# Soundtrap_IMU_board_v4_RXTX_switch.net
KiCad netlist of a schematic drawn in EAGLE
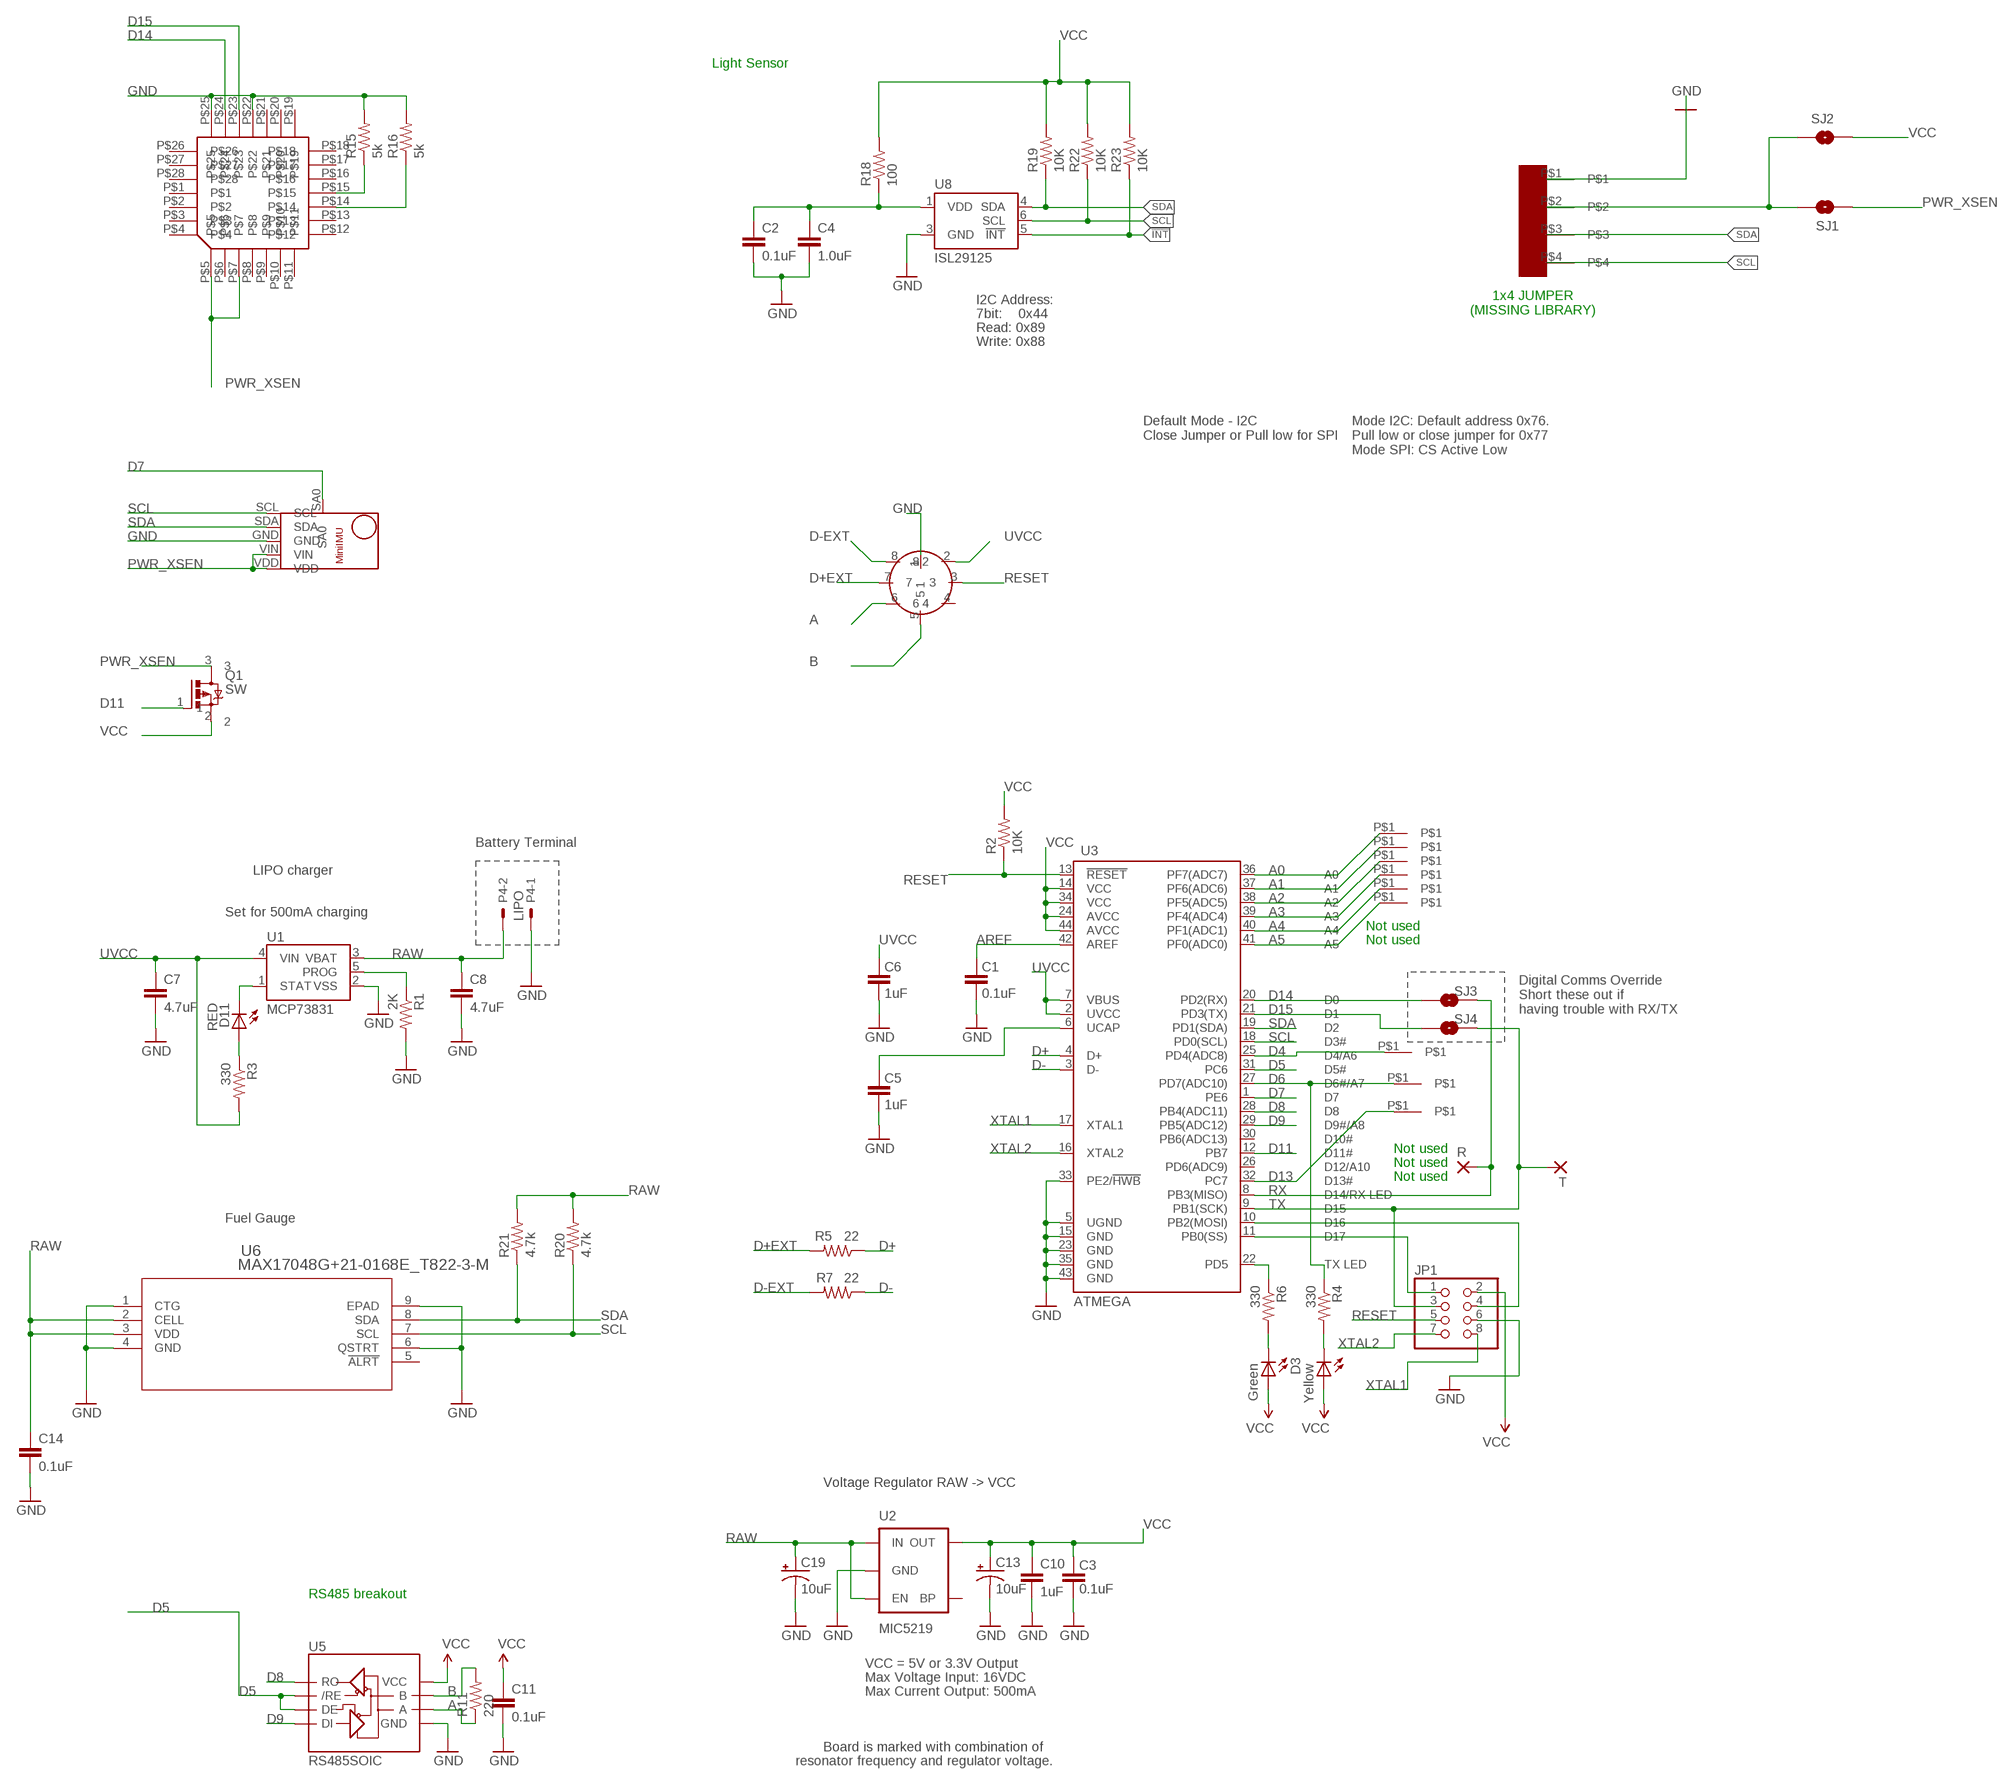
[diagram p0: schematic, sheet 1]

(export (version "E")
  (design (tool "Eeschema 10.0.6"))
  (components
    (comp (ref "C1")
      (value "0.1uF")
      (footprint "eagle-import:0603-CAP")
      (libsource (lib "eagle-import") (part "CAP0603-CAP"))
    )
    (comp (ref "C2")
      (value "0.1uF")
      (footprint "eagle-import:0603-CAP")
      (libsource (lib "eagle-import") (part "0.1UF-25V(+80/-20%)(0603)"))
    )
    (comp (ref "C3")
      (value "0.1uF")
      (footprint "eagle-import:0603-CAP")
      (libsource (lib "eagle-import") (part "CAP0603-CAP"))
    )
    (comp (ref "C4")
      (value "1.0uF")
      (footprint "eagle-import:0603-CAP")
      (libsource (lib "eagle-import") (part "1.0UF-16V-10%(0603)"))
    )
    (comp (ref "C5")
      (value "1uF")
      (footprint "eagle-import:0603-CAP")
      (libsource (lib "eagle-import") (part "CAP0603-CAP"))
    )
    (comp (ref "C6")
      (value "1uF")
      (footprint "eagle-import:0603-CAP")
      (libsource (lib "eagle-import") (part "CAP0603-CAP"))
    )
    (comp (ref "C7")
      (value "4.7uF")
      (footprint "eagle-import:0402-CAP")
      (libsource (lib "eagle-import") (part "CAP0402-CAP"))
    )
    (comp (ref "C8")
      (value "4.7uF")
      (footprint "eagle-import:0402-CAP")
      (libsource (lib "eagle-import") (part "CAP0402-CAP"))
    )
    (comp (ref "C10")
      (value "1uF")
      (footprint "eagle-import:0603-CAP")
      (libsource (lib "eagle-import") (part "CAP0603-CAP"))
    )
    (comp (ref "C11")
      (value "0.1uF")
      (footprint "eagle-import:0402-CAP")
      (libsource (lib "eagle-import") (part "CAP0402-CAP"))
    )
    (comp (ref "C13")
      (value "10uF")
      (footprint "eagle-import:EIA3216")
      (libsource (lib "eagle-import") (part "CAP_POL1206"))
    )
    (comp (ref "C14")
      (value "0.1uF")
      (footprint "eagle-import:0402-CAP")
      (libsource (lib "eagle-import") (part "CAP0402-CAP"))
    )
    (comp (ref "C19")
      (value "10uF")
      (footprint "eagle-import:EIA3216")
      (libsource (lib "eagle-import") (part "CAP_POL1206"))
    )
    (comp (ref "D1")
      (value "Yellow")
      (footprint "eagle-import:LED-0603")
      (libsource (lib "eagle-import") (part "LED0603"))
    )
    (comp (ref "D3")
      (value "Green")
      (footprint "eagle-import:LED-0603")
      (libsource (lib "eagle-import") (part "LED0603"))
    )
    (comp (ref "D11")
      (value "RED")
      (footprint "eagle-import:LED-0603")
      (libsource (lib "eagle-import") (part "LED0603"))
    )
    (comp (ref "JP1")
      (value "PINHD-2X4")
      (footprint "eagle-import:2X04")
      (libsource (lib "eagle-import") (part "PINHD-2X4"))
    )
    (comp (ref "P1")
      (value "SUBCON_MICRO_8_EDGE_ORDERED")
      (footprint "eagle-import:SUBCON_MICRO_8_EDGE")
      (libsource (lib "eagle-import") (part "SUBCON_MICRO_8_EDGE_ORDERED"))
    )
    (comp (ref "P2")
      (value "MINI_IMU")
      (footprint "eagle-import:MINI_IMU")
      (libsource (lib "eagle-import") (part "MINI_IMU"))
    )
    (comp (ref "P3")
      (value "EXT_PRES")
      (footprint "eagle-import:EXT_PRES")
      (libsource (lib "eagle-import") (part "EXT_PRES"))
    )
    (comp (ref "P4")
      (value "LIPO")
      (footprint "eagle-import:22-23-2021")
      (fields (field (name "MF") "MOLEX") (field (name "MPN") "22-23-2021"))
      (libsource (lib "eagle-import") (part "22-23-2021"))
    )
    (comp (ref "Q1")
      (value "SW")
      (footprint "eagle-import:SOT23")
      (libsource (lib "eagle-import") (part "INFINEON_BSS84P"))
    )
    (comp (ref "R")
      (value "1,6/0,9")
      (footprint "eagle-import:1,6_0,9")
      (libsource (lib "eagle-import") (part "1,6/0,9"))
    )
    (comp (ref "R1")
      (value "2K")
      (footprint "eagle-import:0402-RES")
      (libsource (lib "eagle-import") (part "RESISTOR0402-RES"))
    )
    (comp (ref "R2")
      (value "10K")
      (footprint "eagle-import:0603-RES")
      (libsource (lib "eagle-import") (part "RESISTOR0603-RES"))
    )
    (comp (ref "R3")
      (value "330")
      (footprint "eagle-import:0402-RES")
      (libsource (lib "eagle-import") (part "RESISTOR0402-RES"))
    )
    (comp (ref "R4")
      (value "330")
      (footprint "eagle-import:0603-RES")
      (libsource (lib "eagle-import") (part "RESISTOR0603-RES"))
    )
    (comp (ref "R5")
      (value "22")
      (footprint "eagle-import:0603-RES")
      (libsource (lib "eagle-import") (part "RESISTOR0603-RES"))
    )
    (comp (ref "R6")
      (value "330")
      (footprint "eagle-import:0603-RES")
      (libsource (lib "eagle-import") (part "RESISTOR0603-RES"))
    )
    (comp (ref "R7")
      (value "22")
      (footprint "eagle-import:0603-RES")
      (libsource (lib "eagle-import") (part "RESISTOR0603-RES"))
    )
    (comp (ref "R11")
      (value "220")
      (footprint "eagle-import:0402-RES")
      (libsource (lib "eagle-import") (part "RESISTOR0402-RES"))
    )
    (comp (ref "R15")
      (value "5k")
      (footprint "eagle-import:R0603")
      (libsource (lib "eagle-import") (part "R-US_R0603"))
    )
    (comp (ref "R16")
      (value "5k")
      (footprint "eagle-import:R0603")
      (libsource (lib "eagle-import") (part "R-US_R0603"))
    )
    (comp (ref "R18")
      (value "100")
      (footprint "eagle-import:0603-RES")
      (libsource (lib "eagle-import") (part "100OHM1/10W1%(0603)"))
    )
    (comp (ref "R19")
      (value "10K")
      (footprint "eagle-import:0603-RES")
      (libsource (lib "eagle-import") (part "10KOHM1/10W1%(0603)0603"))
    )
    (comp (ref "R20")
      (value "4.7k")
      (footprint "eagle-import:0402-RES")
      (libsource (lib "eagle-import") (part "RESISTOR0402-RES"))
    )
    (comp (ref "R21")
      (value "4.7k")
      (footprint "eagle-import:0402-RES")
      (libsource (lib "eagle-import") (part "RESISTOR0402-RES"))
    )
    (comp (ref "R22")
      (value "10K")
      (footprint "eagle-import:0603-RES")
      (libsource (lib "eagle-import") (part "10KOHM1/10W1%(0603)0603"))
    )
    (comp (ref "R23")
      (value "10K")
      (footprint "eagle-import:0603-RES")
      (libsource (lib "eagle-import") (part "10KOHM1/10W1%(0603)0603"))
    )
    (comp (ref "SJ1")
      (value "SJ1")
      (footprint "eagle-import:SJ_2S-NO")
      (libsource (lib "eagle-import") (part "SOLDERJUMPERNO"))
    )
    (comp (ref "SJ2")
      (value "3v3")
      (footprint "eagle-import:SJ_2S-NO")
      (libsource (lib "eagle-import") (part "SOLDERJUMPERNO"))
    )
    (comp (ref "SJ3")
      (value "SJ1")
      (footprint "eagle-import:SJ_2S-NO")
      (libsource (lib "eagle-import") (part "SOLDERJUMPERNO"))
    )
    (comp (ref "SJ4")
      (value "SJ1")
      (footprint "eagle-import:SJ_2S-NO")
      (libsource (lib "eagle-import") (part "SOLDERJUMPERNO"))
    )
    (comp (ref "T")
      (value "1,6/0,9")
      (footprint "eagle-import:1,6_0,9")
      (libsource (lib "eagle-import") (part "1,6/0,9"))
    )
    (comp (ref "U$5")
      (value "D4")
      (footprint "eagle-import:TEST_POINT")
      (libsource (lib "eagle-import") (part "TEST_POINT"))
    )
    (comp (ref "U$6")
      (value "TEST_POINT")
      (footprint "eagle-import:TEST_POINT")
      (libsource (lib "eagle-import") (part "TEST_POINT"))
    )
    (comp (ref "U$7")
      (value "TEST_POINT")
      (footprint "eagle-import:TEST_POINT")
      (libsource (lib "eagle-import") (part "TEST_POINT"))
    )
    (comp (ref "U$8")
      (value "TEST_POINT")
      (footprint "eagle-import:TEST_POINT")
      (libsource (lib "eagle-import") (part "TEST_POINT"))
    )
    (comp (ref "U$9")
      (value "TEST_POINT")
      (footprint "eagle-import:TEST_POINT")
      (libsource (lib "eagle-import") (part "TEST_POINT"))
    )
    (comp (ref "U$10")
      (value "TEST_POINT")
      (footprint "eagle-import:TEST_POINT")
      (libsource (lib "eagle-import") (part "TEST_POINT"))
    )
    (comp (ref "U$11")
      (value "TEST_POINT")
      (footprint "eagle-import:TEST_POINT")
      (libsource (lib "eagle-import") (part "TEST_POINT"))
    )
    (comp (ref "U$12")
      (value "TEST_POINT")
      (footprint "eagle-import:TEST_POINT")
      (libsource (lib "eagle-import") (part "TEST_POINT"))
    )
    (comp (ref "U$13")
      (value "TEST_POINT")
      (footprint "eagle-import:TEST_POINT")
      (libsource (lib "eagle-import") (part "TEST_POINT"))
    )
    (comp (ref "U1")
      (value "MCP73831")
      (footprint "eagle-import:SOT23-5")
      (libsource (lib "eagle-import") (part "MCP73831"))
    )
    (comp (ref "U2")
      (value "MIC5219")
      (footprint "eagle-import:SOT23-5")
      (libsource (lib "eagle-import") (part "V_REG_LDOSMD"))
    )
    (comp (ref "U3")
      (value "ATMEGA")
      (footprint "eagle-import:QFN-44-NOPAD_1_1-OUTFAKES")
      (libsource (lib "eagle-import") (part "ATMEGA32U4OUTFAKES"))
    )
    (comp (ref "U5")
      (value "RS485SOIC")
      (footprint "eagle-import:SO08")
      (libsource (lib "eagle-import") (part "RS485SOIC"))
    )
    (comp (ref "U6")
      (value "MAX17048G+21-0168E_T822-3-M")
      (footprint "eagle-import:21-0168E_T822-3-M")
      (fields (field (name "MANUFACTURER_PART_NUMBER") "MAX17048G+"))
      (libsource (lib "eagle-import") (part "MAX17048G+21-0168E_T822-3-M"))
    )
    (comp (ref "U7")
      (value "XSENSE")
      (footprint "eagle-import:MC-28PLCC-SMT")
      (libsource (lib "eagle-import") (part "XSENSE"))
    )
    (comp (ref "U8")
      (value "ISL29125")
      (footprint "eagle-import:ODFN-LD-6")
      (libsource (lib "eagle-import") (part "ISL29125"))
    )
  )
  (nets
    (net (code "1") (name "/A") (class "Default")
      (node (ref "P1") (pin "6") (pinfunction "6_6") (pintype "bidirectional"))
      (node (ref "R11") (pin "1") (pinfunction "1_1") (pintype "passive"))
      (node (ref "U5") (pin "6") (pinfunction "A_6") (pintype "bidirectional"))
    )
    (net (code "2") (name "/A0") (class "Default")
      (node (ref "U$8") (pin "P$1") (pinfunction "P$1_P$1") (pintype "bidirectional"))
      (node (ref "U3") (pin "36") (pinfunction "PF7(ADC7)_36") (pintype "bidirectional"))
    )
    (net (code "3") (name "/A1") (class "Default")
      (node (ref "U$9") (pin "P$1") (pinfunction "P$1_P$1") (pintype "bidirectional"))
      (node (ref "U3") (pin "37") (pinfunction "PF6(ADC6)_37") (pintype "bidirectional"))
    )
    (net (code "4") (name "/A2") (class "Default")
      (node (ref "U$10") (pin "P$1") (pinfunction "P$1_P$1") (pintype "bidirectional"))
      (node (ref "U3") (pin "38") (pinfunction "PF5(ADC5)_38") (pintype "bidirectional"))
    )
    (net (code "5") (name "/A3") (class "Default")
      (node (ref "U$11") (pin "P$1") (pinfunction "P$1_P$1") (pintype "bidirectional"))
      (node (ref "U3") (pin "39") (pinfunction "PF4(ADC4)_39") (pintype "bidirectional"))
    )
    (net (code "6") (name "/A4") (class "Default")
      (node (ref "U$12") (pin "P$1") (pinfunction "P$1_P$1") (pintype "bidirectional"))
      (node (ref "U3") (pin "40") (pinfunction "PF1(ADC1)_40") (pintype "bidirectional"))
    )
    (net (code "7") (name "/A5") (class "Default")
      (node (ref "U$13") (pin "P$1") (pinfunction "P$1_P$1") (pintype "bidirectional"))
      (node (ref "U3") (pin "41") (pinfunction "PF0(ADC0)_41") (pintype "bidirectional"))
    )
    (net (code "8") (name "/AREF") (class "Default")
      (node (ref "C1") (pin "2") (pinfunction "2_2") (pintype "passive"))
      (node (ref "U3") (pin "42") (pinfunction "AREF_42") (pintype "bidirectional"))
    )
    (net (code "9") (name "/B") (class "Default")
      (node (ref "P1") (pin "5") (pinfunction "5_5") (pintype "bidirectional"))
      (node (ref "R11") (pin "2") (pinfunction "2_2") (pintype "passive"))
      (node (ref "U5") (pin "7") (pinfunction "B_7") (pintype "bidirectional"))
    )
    (net (code "10") (name "/D+") (class "Default")
      (node (ref "R5") (pin "1") (pinfunction "1_1") (pintype "passive"))
      (node (ref "U3") (pin "4") (pinfunction "D+_4") (pintype "bidirectional"))
    )
    (net (code "11") (name "/D+EXT") (class "Default")
      (node (ref "P1") (pin "7") (pinfunction "7_7") (pintype "bidirectional"))
      (node (ref "R5") (pin "2") (pinfunction "2_2") (pintype "passive"))
    )
    (net (code "12") (name "/D-") (class "Default")
      (node (ref "R7") (pin "1") (pinfunction "1_1") (pintype "passive"))
      (node (ref "U3") (pin "3") (pinfunction "D-_3") (pintype "bidirectional"))
    )
    (net (code "13") (name "/D-EXT") (class "Default")
      (node (ref "P1") (pin "8") (pinfunction "8_8") (pintype "bidirectional"))
      (node (ref "R7") (pin "2") (pinfunction "2_2") (pintype "passive"))
    )
    (net (code "14") (name "/D4") (class "Default")
      (node (ref "U$5") (pin "P$1") (pinfunction "P$1_P$1") (pintype "bidirectional"))
      (node (ref "U3") (pin "25") (pinfunction "PD4(ADC8)_25") (pintype "bidirectional"))
    )
    (net (code "15") (name "/D5") (class "Default")
      (node (ref "U3") (pin "31") (pinfunction "PC6_31") (pintype "bidirectional"))
      (node (ref "U5") (pin "2") (pinfunction "/RE_2") (pintype "bidirectional"))
      (node (ref "U5") (pin "3") (pinfunction "DE_3") (pintype "bidirectional"))
    )
    (net (code "16") (name "/D6") (class "Default")
      (node (ref "R4") (pin "1") (pinfunction "1_1") (pintype "passive"))
      (node (ref "U$6") (pin "P$1") (pinfunction "P$1_P$1") (pintype "bidirectional"))
      (node (ref "U3") (pin "27") (pinfunction "PD7(ADC10)_27") (pintype "bidirectional"))
    )
    (net (code "17") (name "/D7") (class "Default")
      (node (ref "P2") (pin "SA0") (pinfunction "SA0_SA0") (pintype "bidirectional"))
      (node (ref "U3") (pin "1") (pinfunction "PE6_1") (pintype "bidirectional"))
    )
    (net (code "18") (name "/D8") (class "Default")
      (node (ref "U3") (pin "28") (pinfunction "PB4(ADC11)_28") (pintype "bidirectional"))
      (node (ref "U5") (pin "1") (pinfunction "RO_1") (pintype "bidirectional"))
    )
    (net (code "19") (name "/D9") (class "Default")
      (node (ref "U3") (pin "29") (pinfunction "PB5(ADC12)_29") (pintype "bidirectional"))
      (node (ref "U5") (pin "4") (pinfunction "DI_4") (pintype "bidirectional"))
    )
    (net (code "20") (name "/D11") (class "Default")
      (node (ref "Q1") (pin "1") (pinfunction "1_1") (pintype "input"))
      (node (ref "U3") (pin "12") (pinfunction "PB7_12") (pintype "bidirectional"))
    )
    (net (code "21") (name "/D13") (class "Default")
      (node (ref "U$7") (pin "P$1") (pinfunction "P$1_P$1") (pintype "bidirectional"))
      (node (ref "U3") (pin "32") (pinfunction "PC7_32") (pintype "bidirectional"))
    )
    (net (code "22") (name "/D14") (class "Default")
      (node (ref "SJ3") (pin "2") (pinfunction "2_2") (pintype "passive"))
      (node (ref "U3") (pin "20") (pinfunction "PD2(RX)_20") (pintype "bidirectional"))
      (node (ref "U7") (pin "P$24") (pinfunction "P$24_P$24") (pintype "bidirectional"))
    )
    (net (code "23") (name "/D15") (class "Default")
      (node (ref "SJ4") (pin "2") (pinfunction "2_2") (pintype "passive"))
      (node (ref "U3") (pin "21") (pinfunction "PD3(TX)_21") (pintype "bidirectional"))
      (node (ref "U7") (pin "P$23") (pinfunction "P$23_P$23") (pintype "bidirectional"))
    )
    (net (code "24") (name "/PWR_XSEN") (class "Default")
      (node (ref "P2") (pin "VDD") (pinfunction "VDD_VDD") (pintype "power_in"))
      (node (ref "P2") (pin "VIN") (pinfunction "VIN_VIN") (pintype "power_in"))
      (node (ref "Q1") (pin "3") (pinfunction "3_3") (pintype "output"))
      (node (ref "SJ1") (pin "1") (pinfunction "1_1") (pintype "passive"))
      (node (ref "U7") (pin "P$5") (pinfunction "P$5_P$5") (pintype "bidirectional"))
      (node (ref "U7") (pin "P$7") (pinfunction "P$7_P$7") (pintype "bidirectional"))
    )
    (net (code "25") (name "/RAW") (class "Default")
      (node (ref "C14") (pin "1") (pinfunction "1_1") (pintype "passive"))
      (node (ref "C19") (pin "A") (pinfunction "+_A") (pintype "passive"))
      (node (ref "C8") (pin "1") (pinfunction "1_1") (pintype "passive"))
      (node (ref "P4") (pin "2") (pinfunction "S_2") (pintype "passive"))
      (node (ref "R20") (pin "2") (pinfunction "2_2") (pintype "passive"))
      (node (ref "R21") (pin "2") (pinfunction "2_2") (pintype "passive"))
      (node (ref "U1") (pin "3") (pinfunction "VBAT_3") (pintype "power_in"))
      (node (ref "U2") (pin "1") (pinfunction "IN_1") (pintype "input"))
      (node (ref "U2") (pin "3") (pinfunction "EN_3") (pintype "input"))
      (node (ref "U6") (pin "2") (pinfunction "CELL_2") (pintype "passive"))
      (node (ref "U6") (pin "3") (pinfunction "VDD_3") (pintype "power_in"))
    )
    (net (code "26") (name "/RESET") (class "Default")
      (node (ref "JP1") (pin "5") (pinfunction "5_5") (pintype "passive"))
      (node (ref "P1") (pin "3") (pinfunction "3_3") (pintype "bidirectional"))
      (node (ref "R2") (pin "1") (pinfunction "1_1") (pintype "passive"))
      (node (ref "U3") (pin "13") (pinfunction "~{RESET}_13") (pintype "bidirectional"))
    )
    (net (code "27") (name "/RX") (class "Default")
      (node (ref "R") (pin "1") (pinfunction "P_1") (pintype "passive"))
      (node (ref "SJ3") (pin "1") (pinfunction "1_1") (pintype "passive"))
      (node (ref "U3") (pin "8") (pinfunction "PB3(MISO)_8") (pintype "bidirectional"))
    )
    (net (code "28") (name "/TX") (class "Default")
      (node (ref "JP1") (pin "3") (pinfunction "3_3") (pintype "passive"))
      (node (ref "SJ4") (pin "1") (pinfunction "1_1") (pintype "passive"))
      (node (ref "T") (pin "1") (pinfunction "P_1") (pintype "passive"))
      (node (ref "U3") (pin "9") (pinfunction "PB1(SCK)_9") (pintype "bidirectional"))
    )
    (net (code "29") (name "/UVCC") (class "Default")
      (node (ref "C6") (pin "2") (pinfunction "2_2") (pintype "passive"))
      (node (ref "C7") (pin "1") (pinfunction "1_1") (pintype "passive"))
      (node (ref "P1") (pin "2") (pinfunction "2_2") (pintype "bidirectional"))
      (node (ref "R3") (pin "2") (pinfunction "2_2") (pintype "passive"))
      (node (ref "U1") (pin "4") (pinfunction "VIN_4") (pintype "power_in"))
      (node (ref "U3") (pin "2") (pinfunction "UVCC_2") (pintype "bidirectional"))
      (node (ref "U3") (pin "7") (pinfunction "VBUS_7") (pintype "bidirectional"))
    )
    (net (code "30") (name "/XTAL1") (class "Default")
      (node (ref "JP1") (pin "8") (pinfunction "8_8") (pintype "passive"))
      (node (ref "U3") (pin "17") (pinfunction "XTAL1_17") (pintype "bidirectional"))
    )
    (net (code "31") (name "/XTAL2") (class "Default")
      (node (ref "JP1") (pin "7") (pinfunction "7_7") (pintype "passive"))
      (node (ref "U3") (pin "16") (pinfunction "XTAL2_16") (pintype "bidirectional"))
    )
    (net (code "32") (name "/~{INT}") (class "Default")
      (node (ref "R23") (pin "1") (pinfunction "1_1") (pintype "passive"))
      (node (ref "U8") (pin "5") (pinfunction "~{INT}_5") (pintype "bidirectional"))
    )
    (net (code "33") (name "GND") (class "Default")
      (node (ref "C1") (pin "1") (pinfunction "1_1") (pintype "passive"))
      (node (ref "C10") (pin "2") (pinfunction "2_2") (pintype "passive"))
      (node (ref "C11") (pin "2") (pinfunction "2_2") (pintype "passive"))
      (node (ref "C13") (pin "C") (pinfunction "-_C") (pintype "passive"))
      (node (ref "C14") (pin "2") (pinfunction "2_2") (pintype "passive"))
      (node (ref "C19") (pin "C") (pinfunction "-_C") (pintype "passive"))
      (node (ref "C2") (pin "2") (pinfunction "2_2") (pintype "passive"))
      (node (ref "C3") (pin "1") (pinfunction "1_1") (pintype "passive"))
      (node (ref "C4") (pin "2") (pinfunction "2_2") (pintype "passive"))
      (node (ref "C5") (pin "1") (pinfunction "1_1") (pintype "passive"))
      (node (ref "C6") (pin "1") (pinfunction "1_1") (pintype "passive"))
      (node (ref "C7") (pin "2") (pinfunction "2_2") (pintype "passive"))
      (node (ref "C8") (pin "2") (pinfunction "2_2") (pintype "passive"))
      (node (ref "JP1") (pin "6") (pinfunction "6_6") (pintype "passive"))
      (node (ref "P1") (pin "1") (pinfunction "1_1") (pintype "bidirectional"))
      (node (ref "P2") (pin "GND") (pinfunction "GND_GND") (pintype "bidirectional"))
      (node (ref "P3") (pin "P$1") (pinfunction "P$1_P$1") (pintype "bidirectional"))
      (node (ref "P4") (pin "1") (pinfunction "S_1") (pintype "passive"))
      (node (ref "R1") (pin "2") (pinfunction "2_2") (pintype "passive"))
      (node (ref "R15") (pin "2") (pinfunction "2_2") (pintype "passive"))
      (node (ref "R16") (pin "2") (pinfunction "2_2") (pintype "passive"))
      (node (ref "U1") (pin "2") (pinfunction "VSS_2") (pintype "power_in"))
      (node (ref "U2") (pin "2") (pinfunction "GND_2") (pintype "input"))
      (node (ref "U3") (pin "15") (pinfunction "GND_15") (pintype "bidirectional"))
      (node (ref "U3") (pin "23") (pinfunction "GND_23") (pintype "bidirectional"))
      (node (ref "U3") (pin "33") (pinfunction "PE2/~{HWB}_33") (pintype "bidirectional"))
      (node (ref "U3") (pin "35") (pinfunction "GND_35") (pintype "bidirectional"))
      (node (ref "U3") (pin "43") (pinfunction "GND_43") (pintype "bidirectional"))
      (node (ref "U3") (pin "5") (pinfunction "UGND_5") (pintype "bidirectional"))
      (node (ref "U5") (pin "5") (pinfunction "GND_5") (pintype "bidirectional"))
      (node (ref "U6") (pin "1") (pinfunction "CTG_1") (pintype "passive"))
      (node (ref "U6") (pin "4") (pinfunction "GND_4") (pintype "power_in"))
      (node (ref "U6") (pin "6") (pinfunction "QSTRT_6") (pintype "input"))
      (node (ref "U6") (pin "9") (pinfunction "EPAD_9") (pintype "passive"))
      (node (ref "U7") (pin "P$22") (pinfunction "P$22_P$22") (pintype "bidirectional"))
      (node (ref "U7") (pin "P$25") (pinfunction "P$25_P$25") (pintype "bidirectional"))
      (node (ref "U8") (pin "3") (pinfunction "GND_3") (pintype "bidirectional"))
    )
    (net (code "34") (name "Net-(D1-PadC)") (class "Default")
      (node (ref "D1") (pin "C") (pinfunction "C_C") (pintype "passive"))
      (node (ref "R4") (pin "2") (pinfunction "2_2") (pintype "passive"))
    )
    (net (code "35") (name "Net-(D3-PadC)") (class "Default")
      (node (ref "D3") (pin "C") (pinfunction "C_C") (pintype "passive"))
      (node (ref "R6") (pin "2") (pinfunction "2_2") (pintype "passive"))
    )
    (net (code "36") (name "Net-(D11-PadA)") (class "Default")
      (node (ref "D11") (pin "A") (pinfunction "A_A") (pintype "passive"))
      (node (ref "R3") (pin "1") (pinfunction "1_1") (pintype "passive"))
    )
    (net (code "37") (name "Net-(P3-PadP$2)") (class "Default")
      (node (ref "P3") (pin "P$2") (pinfunction "P$2_P$2") (pintype "bidirectional"))
      (node (ref "SJ1") (pin "2") (pinfunction "2_2") (pintype "passive"))
      (node (ref "SJ2") (pin "1") (pinfunction "1_1") (pintype "passive"))
    )
    (net (code "38") (name "Net-(R15-Pad1)") (class "Default")
      (node (ref "R15") (pin "1") (pinfunction "1_1") (pintype "passive"))
      (node (ref "U7") (pin "P$15") (pinfunction "P$15_P$15") (pintype "bidirectional"))
    )
    (net (code "39") (name "Net-(R16-Pad1)") (class "Default")
      (node (ref "R16") (pin "1") (pinfunction "1_1") (pintype "passive"))
      (node (ref "U7") (pin "P$14") (pinfunction "P$14_P$14") (pintype "bidirectional"))
    )
    (net (code "40") (name "Net-(U1-PROG)") (class "Default")
      (node (ref "R1") (pin "1") (pinfunction "1_1") (pintype "passive"))
      (node (ref "U1") (pin "5") (pinfunction "PROG_5") (pintype "input"))
    )
    (net (code "41") (name "Net-(U1-STAT)") (class "Default")
      (node (ref "D11") (pin "C") (pinfunction "C_C") (pintype "passive"))
      (node (ref "U1") (pin "1") (pinfunction "STAT_1") (pintype "output"))
    )
    (net (code "42") (name "Net-(U3-PB0(SS))") (class "Default")
      (node (ref "JP1") (pin "1") (pinfunction "1_1") (pintype "passive"))
      (node (ref "U3") (pin "11") (pinfunction "PB0(SS)_11") (pintype "bidirectional"))
    )
    (net (code "43") (name "Net-(U3-PB2(MOSI))") (class "Default")
      (node (ref "JP1") (pin "4") (pinfunction "4_4") (pintype "passive"))
      (node (ref "U3") (pin "10") (pinfunction "PB2(MOSI)_10") (pintype "bidirectional"))
    )
    (net (code "44") (name "Net-(U3-PD5)") (class "Default")
      (node (ref "R6") (pin "1") (pinfunction "1_1") (pintype "passive"))
      (node (ref "U3") (pin "22") (pinfunction "PD5_22") (pintype "bidirectional"))
    )
    (net (code "45") (name "Net-(U3-UCAP)") (class "Default")
      (node (ref "C5") (pin "2") (pinfunction "2_2") (pintype "passive"))
      (node (ref "U3") (pin "6") (pinfunction "UCAP_6") (pintype "bidirectional"))
    )
    (net (code "46") (name "Net-(U8-VDD)") (class "Default")
      (node (ref "C2") (pin "1") (pinfunction "1_1") (pintype "passive"))
      (node (ref "C4") (pin "1") (pinfunction "1_1") (pintype "passive"))
      (node (ref "R18") (pin "1") (pinfunction "1_1") (pintype "passive"))
      (node (ref "U8") (pin "1") (pinfunction "VDD_1") (pintype "bidirectional"))
    )
    (net (code "47") (name "SCL") (class "Default")
      (node (ref "P2") (pin "SCL") (pinfunction "SCL_SCL") (pintype "bidirectional"))
      (node (ref "P3") (pin "P$4") (pinfunction "P$4_P$4") (pintype "bidirectional"))
      (node (ref "R20") (pin "1") (pinfunction "1_1") (pintype "passive"))
      (node (ref "R22") (pin "1") (pinfunction "1_1") (pintype "passive"))
      (node (ref "U3") (pin "18") (pinfunction "PD0(SCL)_18") (pintype "bidirectional"))
      (node (ref "U6") (pin "7") (pinfunction "SCL_7") (pintype "input"))
      (node (ref "U8") (pin "6") (pinfunction "SCL_6") (pintype "bidirectional"))
    )
    (net (code "48") (name "SDA") (class "Default")
      (node (ref "P2") (pin "SDA") (pinfunction "SDA_SDA") (pintype "bidirectional"))
      (node (ref "P3") (pin "P$3") (pinfunction "P$3_P$3") (pintype "bidirectional"))
      (node (ref "R19") (pin "1") (pinfunction "1_1") (pintype "passive"))
      (node (ref "R21") (pin "1") (pinfunction "1_1") (pintype "passive"))
      (node (ref "U3") (pin "19") (pinfunction "PD1(SDA)_19") (pintype "bidirectional"))
      (node (ref "U6") (pin "8") (pinfunction "SDA_8") (pintype "bidirectional"))
      (node (ref "U8") (pin "4") (pinfunction "SDA_4") (pintype "bidirectional"))
    )
    (net (code "49") (name "VCC") (class "Default")
      (node (ref "C10") (pin "1") (pinfunction "1_1") (pintype "passive"))
      (node (ref "C11") (pin "1") (pinfunction "1_1") (pintype "passive"))
      (node (ref "C13") (pin "A") (pinfunction "+_A") (pintype "passive"))
      (node (ref "C3") (pin "2") (pinfunction "2_2") (pintype "passive"))
      (node (ref "D1") (pin "A") (pinfunction "A_A") (pintype "passive"))
      (node (ref "D3") (pin "A") (pinfunction "A_A") (pintype "passive"))
      (node (ref "JP1") (pin "2") (pinfunction "2_2") (pintype "passive"))
      (node (ref "Q1") (pin "2") (pinfunction "2_2") (pintype "input"))
      (node (ref "R18") (pin "2") (pinfunction "2_2") (pintype "passive"))
      (node (ref "R19") (pin "2") (pinfunction "2_2") (pintype "passive"))
      (node (ref "R2") (pin "2") (pinfunction "2_2") (pintype "passive"))
      (node (ref "R22") (pin "2") (pinfunction "2_2") (pintype "passive"))
      (node (ref "R23") (pin "2") (pinfunction "2_2") (pintype "passive"))
      (node (ref "SJ2") (pin "2") (pinfunction "2_2") (pintype "passive"))
      (node (ref "U2") (pin "5") (pinfunction "OUT_5") (pintype "passive"))
      (node (ref "U3") (pin "14") (pinfunction "VCC_14") (pintype "bidirectional"))
      (node (ref "U3") (pin "24") (pinfunction "AVCC_24") (pintype "bidirectional"))
      (node (ref "U3") (pin "34") (pinfunction "VCC_34") (pintype "bidirectional"))
      (node (ref "U3") (pin "44") (pinfunction "AVCC_44") (pintype "bidirectional"))
      (node (ref "U5") (pin "8") (pinfunction "VCC_8") (pintype "bidirectional"))
    )
    (net (code "50") (name "unconnected-(P1-Pad4)") (class "Default")
      (node (ref "P1") (pin "4") (pinfunction "4_4") (pintype "bidirectional"))
    )
    (net (code "51") (name "unconnected-(U2-BP-Pad4)") (class "Default")
      (node (ref "U2") (pin "4") (pinfunction "BP_4") (pintype "input"))
    )
    (net (code "52") (name "unconnected-(U3-PB6(ADC13)-Pad30)") (class "Default")
      (node (ref "U3") (pin "30") (pinfunction "PB6(ADC13)_30") (pintype "bidirectional"))
    )
    (net (code "53") (name "unconnected-(U3-PD6(ADC9)-Pad26)") (class "Default")
      (node (ref "U3") (pin "26") (pinfunction "PD6(ADC9)_26") (pintype "bidirectional"))
    )
    (net (code "54") (name "unconnected-(U6-~{ALRT}-Pad5)") (class "Default")
      (node (ref "U6") (pin "5") (pinfunction "~{ALRT}_5") (pintype "output"))
    )
    (net (code "55") (name "unconnected-(U7-PadP$1)") (class "Default")
      (node (ref "U7") (pin "P$1") (pinfunction "P$1_P$1") (pintype "bidirectional"))
    )
    (net (code "56") (name "unconnected-(U7-PadP$2)") (class "Default")
      (node (ref "U7") (pin "P$2") (pinfunction "P$2_P$2") (pintype "bidirectional"))
    )
    (net (code "57") (name "unconnected-(U7-PadP$3)") (class "Default")
      (node (ref "U7") (pin "P$3") (pinfunction "P$3_P$3") (pintype "bidirectional"))
    )
    (net (code "58") (name "unconnected-(U7-PadP$4)") (class "Default")
      (node (ref "U7") (pin "P$4") (pinfunction "P$4_P$4") (pintype "bidirectional"))
    )
    (net (code "59") (name "unconnected-(U7-PadP$6)") (class "Default")
      (node (ref "U7") (pin "P$6") (pinfunction "P$6_P$6") (pintype "bidirectional"))
    )
    (net (code "60") (name "unconnected-(U7-PadP$8)") (class "Default")
      (node (ref "U7") (pin "P$8") (pinfunction "P$8_P$8") (pintype "bidirectional"))
    )
    (net (code "61") (name "unconnected-(U7-PadP$9)") (class "Default")
      (node (ref "U7") (pin "P$9") (pinfunction "P$9_P$9") (pintype "bidirectional"))
    )
    (net (code "62") (name "unconnected-(U7-PadP$10)") (class "Default")
      (node (ref "U7") (pin "P$10") (pinfunction "P$10_P$10") (pintype "bidirectional"))
    )
    (net (code "63") (name "unconnected-(U7-PadP$11)") (class "Default")
      (node (ref "U7") (pin "P$11") (pinfunction "P$11_P$11") (pintype "bidirectional"))
    )
    (net (code "64") (name "unconnected-(U7-PadP$12)") (class "Default")
      (node (ref "U7") (pin "P$12") (pinfunction "P$12_P$12") (pintype "bidirectional"))
    )
    (net (code "65") (name "unconnected-(U7-PadP$13)") (class "Default")
      (node (ref "U7") (pin "P$13") (pinfunction "P$13_P$13") (pintype "bidirectional"))
    )
    (net (code "66") (name "unconnected-(U7-PadP$16)") (class "Default")
      (node (ref "U7") (pin "P$16") (pinfunction "P$16_P$16") (pintype "bidirectional"))
    )
    (net (code "67") (name "unconnected-(U7-PadP$17)") (class "Default")
      (node (ref "U7") (pin "P$17") (pinfunction "P$17_P$17") (pintype "bidirectional"))
    )
    (net (code "68") (name "unconnected-(U7-PadP$18)") (class "Default")
      (node (ref "U7") (pin "P$18") (pinfunction "P$18_P$18") (pintype "bidirectional"))
    )
    (net (code "69") (name "unconnected-(U7-PadP$19)") (class "Default")
      (node (ref "U7") (pin "P$19") (pinfunction "P$19_P$19") (pintype "bidirectional"))
    )
    (net (code "70") (name "unconnected-(U7-PadP$20)") (class "Default")
      (node (ref "U7") (pin "P$20") (pinfunction "P$20_P$20") (pintype "bidirectional"))
    )
    (net (code "71") (name "unconnected-(U7-PadP$21)") (class "Default")
      (node (ref "U7") (pin "P$21") (pinfunction "P$21_P$21") (pintype "bidirectional"))
    )
    (net (code "72") (name "unconnected-(U7-PadP$26)") (class "Default")
      (node (ref "U7") (pin "P$26") (pinfunction "P$26_P$26") (pintype "bidirectional"))
    )
    (net (code "73") (name "unconnected-(U7-PadP$27)") (class "Default")
      (node (ref "U7") (pin "P$27") (pinfunction "P$27_P$27") (pintype "bidirectional"))
    )
    (net (code "74") (name "unconnected-(U7-PadP$28)") (class "Default")
      (node (ref "U7") (pin "P$28") (pinfunction "P$28_P$28") (pintype "bidirectional"))
    )
  )
)
